# Lampu_Otomatis.net
KiCad netlist of a schematic drawn in EAGLE
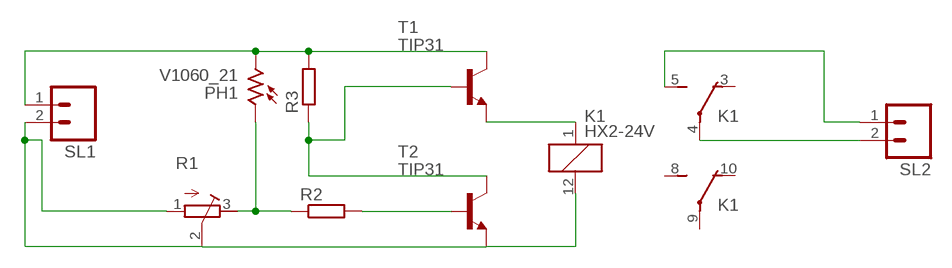
[diagram p0: schematic, sheet 1]

(export (version "E")
  (design (tool "Eeschema 10.0.6"))
  (components
    (comp (ref "K1")
      (value "HX2-24V")
      (footprint "eagle-import:HX")
      (libsource (lib "eagle-import") (part "HX2-24V"))
    )
    (comp (ref "PH1")
      (value "V1060_21")
      (footprint "eagle-import:TO-5_V10")
      (libsource (lib "eagle-import") (part "?1060V_21"))
    )
    (comp (ref "R1")
      (value "R-TRIMM3339P")
      (footprint "eagle-import:RTRIM3339P")
      (libsource (lib "eagle-import") (part "R-TRIMM3339P"))
    )
    (comp (ref "R2")
      (value "R-EU_0207/10")
      (footprint "eagle-import:0207_10")
      (libsource (lib "eagle-import") (part "R-EU_0207/10"))
    )
    (comp (ref "R3")
      (value "R-EU_0207/10")
      (footprint "eagle-import:0207_10")
      (libsource (lib "eagle-import") (part "R-EU_0207/10"))
    )
    (comp (ref "SL1")
      (value "M02")
      (footprint "eagle-import:02P")
      (libsource (lib "eagle-import") (part "M02"))
    )
    (comp (ref "SL2")
      (value "M02")
      (footprint "eagle-import:02P")
      (libsource (lib "eagle-import") (part "M02"))
    )
    (comp (ref "T1")
      (value "TIP31")
      (footprint "eagle-import:TO220")
      (libsource (lib "eagle-import") (part "TIP31"))
    )
    (comp (ref "T2")
      (value "TIP31")
      (footprint "eagle-import:TO220")
      (libsource (lib "eagle-import") (part "TIP31"))
    )
  )
  (nets
    (net (code "1") (name "Net-(K1A-2)") (class "Default")
      (node (ref "K1") (pin "12") (pinfunction "2_12") (pintype "passive"))
      (node (ref "R1") (pin "1") (pinfunction "A_1") (pintype "passive"))
      (node (ref "R1") (pin "2") (pinfunction "S_2") (pintype "passive"))
      (node (ref "SL1") (pin "2") (pinfunction "2_2") (pintype "passive"))
      (node (ref "T2") (pin "3") (pinfunction "E_3") (pintype "passive"))
    )
    (net (code "2") (name "Net-(K1B-P)") (class "Default")
      (node (ref "K1") (pin "4") (pinfunction "P_4") (pintype "passive"))
      (node (ref "SL2") (pin "2") (pinfunction "2_2") (pintype "passive"))
    )
    (net (code "3") (name "Net-(K1B-S)") (class "Default")
      (node (ref "K1") (pin "5") (pinfunction "S_5") (pintype "passive"))
      (node (ref "SL2") (pin "1") (pinfunction "1_1") (pintype "passive"))
    )
    (net (code "4") (name "Net-(R1-E)") (class "Default")
      (node (ref "PH1") (pin "1") (pinfunction "1_1") (pintype "passive"))
      (node (ref "R1") (pin "3") (pinfunction "E_3") (pintype "passive"))
      (node (ref "R2") (pin "1") (pinfunction "1_1") (pintype "passive"))
    )
    (net (code "5") (name "Net-(T1-B)") (class "Default")
      (node (ref "R3") (pin "1") (pinfunction "1_1") (pintype "passive"))
      (node (ref "T1") (pin "1") (pinfunction "B_1") (pintype "passive"))
      (node (ref "T2") (pin "2") (pinfunction "C_2") (pintype "passive"))
    )
    (net (code "6") (name "Net-(T1-C)") (class "Default")
      (node (ref "PH1") (pin "2") (pinfunction "2_2") (pintype "passive"))
      (node (ref "R3") (pin "2") (pinfunction "2_2") (pintype "passive"))
      (node (ref "SL1") (pin "1") (pinfunction "1_1") (pintype "passive"))
      (node (ref "T1") (pin "2") (pinfunction "C_2") (pintype "passive"))
    )
    (net (code "7") (name "Net-(T1-E)") (class "Default")
      (node (ref "K1") (pin "1") (pinfunction "1_1") (pintype "passive"))
      (node (ref "T1") (pin "3") (pinfunction "E_3") (pintype "passive"))
    )
    (net (code "8") (name "Net-(T2-B)") (class "Default")
      (node (ref "R2") (pin "2") (pinfunction "2_2") (pintype "passive"))
      (node (ref "T2") (pin "1") (pinfunction "B_1") (pintype "passive"))
    )
    (net (code "9") (name "unconnected-(K1B-O-Pad3)") (class "Default")
      (node (ref "K1") (pin "3") (pinfunction "O_3") (pintype "passive"))
    )
    (net (code "10") (name "unconnected-(K1C-O-Pad10)") (class "Default")
      (node (ref "K1") (pin "10") (pinfunction "O_10") (pintype "passive"))
    )
    (net (code "11") (name "unconnected-(K1C-P-Pad9)") (class "Default")
      (node (ref "K1") (pin "9") (pinfunction "P_9") (pintype "passive"))
    )
    (net (code "12") (name "unconnected-(K1C-S-Pad8)") (class "Default")
      (node (ref "K1") (pin "8") (pinfunction "S_8") (pintype "passive"))
    )
  )
)
